# weddinginvitation.net
KiCad netlist of a schematic drawn in EAGLE
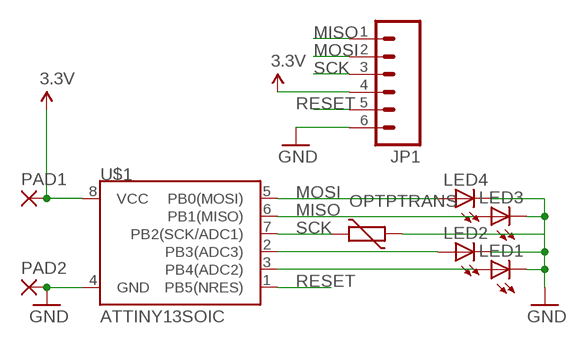
[diagram p0: schematic, sheet 1]

(export (version "E")
  (design (tool "Eeschema 10.0.6"))
  (components
    (comp (ref "JP1")
      (value "M06SMD-FEMALE-V2")
      (footprint "eagle-import:1X06-SMD-FEMALE-V2")
      (libsource (lib "eagle-import") (part "M06SMD-FEMALE-V2"))
    )
    (comp (ref "LED1")
      (value "LED1206")
      (footprint "eagle-import:LED-1206")
      (libsource (lib "eagle-import") (part "LED1206"))
    )
    (comp (ref "LED2")
      (value "LED1206")
      (footprint "eagle-import:LED-1206")
      (libsource (lib "eagle-import") (part "LED1206"))
    )
    (comp (ref "LED3")
      (value "LED1206")
      (footprint "eagle-import:LED-1206")
      (libsource (lib "eagle-import") (part "LED1206"))
    )
    (comp (ref "LED4")
      (value "LED1206")
      (footprint "eagle-import:LED-1206")
      (libsource (lib "eagle-import") (part "LED1206"))
    )
    (comp (ref "OPTPTRANS")
      (value "VARISTORCN0805")
      (footprint "eagle-import:CT_CN0805")
      (libsource (lib "eagle-import") (part "VARISTORCN0805"))
    )
    (comp (ref "PAD1")
      (value "SMD5")
      (footprint "eagle-import:SMD2,54-5,08")
      (libsource (lib "eagle-import") (part "SMD5"))
    )
    (comp (ref "PAD2")
      (value "SMD5")
      (footprint "eagle-import:SMD2,54-5,08")
      (libsource (lib "eagle-import") (part "SMD5"))
    )
    (comp (ref "U$1")
      (value "ATTINY13SOIC")
      (footprint "eagle-import:SO08")
      (libsource (lib "eagle-import") (part "ATTINY13SOIC"))
    )
  )
  (nets
    (net (code "1") (name "/MISO") (class "Default")
      (node (ref "JP1") (pin "1") (pinfunction "1_1") (pintype "passive"))
      (node (ref "LED3") (pin "A") (pinfunction "A_A") (pintype "passive"))
      (node (ref "U$1") (pin "6") (pinfunction "PB1(MISO)_6") (pintype "bidirectional"))
    )
    (net (code "2") (name "/MOSI") (class "Default")
      (node (ref "JP1") (pin "2") (pinfunction "2_2") (pintype "passive"))
      (node (ref "LED4") (pin "A") (pinfunction "A_A") (pintype "passive"))
      (node (ref "U$1") (pin "5") (pinfunction "PB0(MOSI)_5") (pintype "bidirectional"))
    )
    (net (code "3") (name "/RESET") (class "Default")
      (node (ref "JP1") (pin "5") (pinfunction "5_5") (pintype "passive"))
      (node (ref "U$1") (pin "1") (pinfunction "PB5(NRES)_1") (pintype "bidirectional"))
    )
    (net (code "4") (name "/SCK") (class "Default")
      (node (ref "JP1") (pin "3") (pinfunction "3_3") (pintype "passive"))
      (node (ref "OPTPTRANS") (pin "2") (pinfunction "2_2") (pintype "passive"))
      (node (ref "U$1") (pin "7") (pinfunction "PB2(SCK/ADC1)_7") (pintype "bidirectional"))
    )
    (net (code "5") (name "3.3V") (class "Default")
      (node (ref "JP1") (pin "4") (pinfunction "4_4") (pintype "passive"))
      (node (ref "PAD1") (pin "1") (pinfunction "P_1") (pintype "passive"))
      (node (ref "U$1") (pin "8") (pinfunction "VCC_8") (pintype "bidirectional"))
    )
    (net (code "6") (name "GND") (class "Default")
      (node (ref "JP1") (pin "6") (pinfunction "6_6") (pintype "passive"))
      (node (ref "LED1") (pin "C") (pinfunction "C_C") (pintype "passive"))
      (node (ref "LED2") (pin "C") (pinfunction "C_C") (pintype "passive"))
      (node (ref "LED3") (pin "C") (pinfunction "C_C") (pintype "passive"))
      (node (ref "LED4") (pin "C") (pinfunction "C_C") (pintype "passive"))
      (node (ref "OPTPTRANS") (pin "1") (pinfunction "1_1") (pintype "passive"))
      (node (ref "PAD2") (pin "1") (pinfunction "P_1") (pintype "passive"))
      (node (ref "U$1") (pin "4") (pinfunction "GND_4") (pintype "bidirectional"))
    )
    (net (code "7") (name "Net-(U$1-PB3(ADC3))") (class "Default")
      (node (ref "LED2") (pin "A") (pinfunction "A_A") (pintype "passive"))
      (node (ref "U$1") (pin "2") (pinfunction "PB3(ADC3)_2") (pintype "bidirectional"))
    )
    (net (code "8") (name "Net-(U$1-PB4(ADC2))") (class "Default")
      (node (ref "LED1") (pin "A") (pinfunction "A_A") (pintype "passive"))
      (node (ref "U$1") (pin "3") (pinfunction "PB4(ADC2)_3") (pintype "bidirectional"))
    )
  )
)
